# arduino_Uno_shield_bora_lora.net
KiCad netlist of a schematic drawn in EAGLE
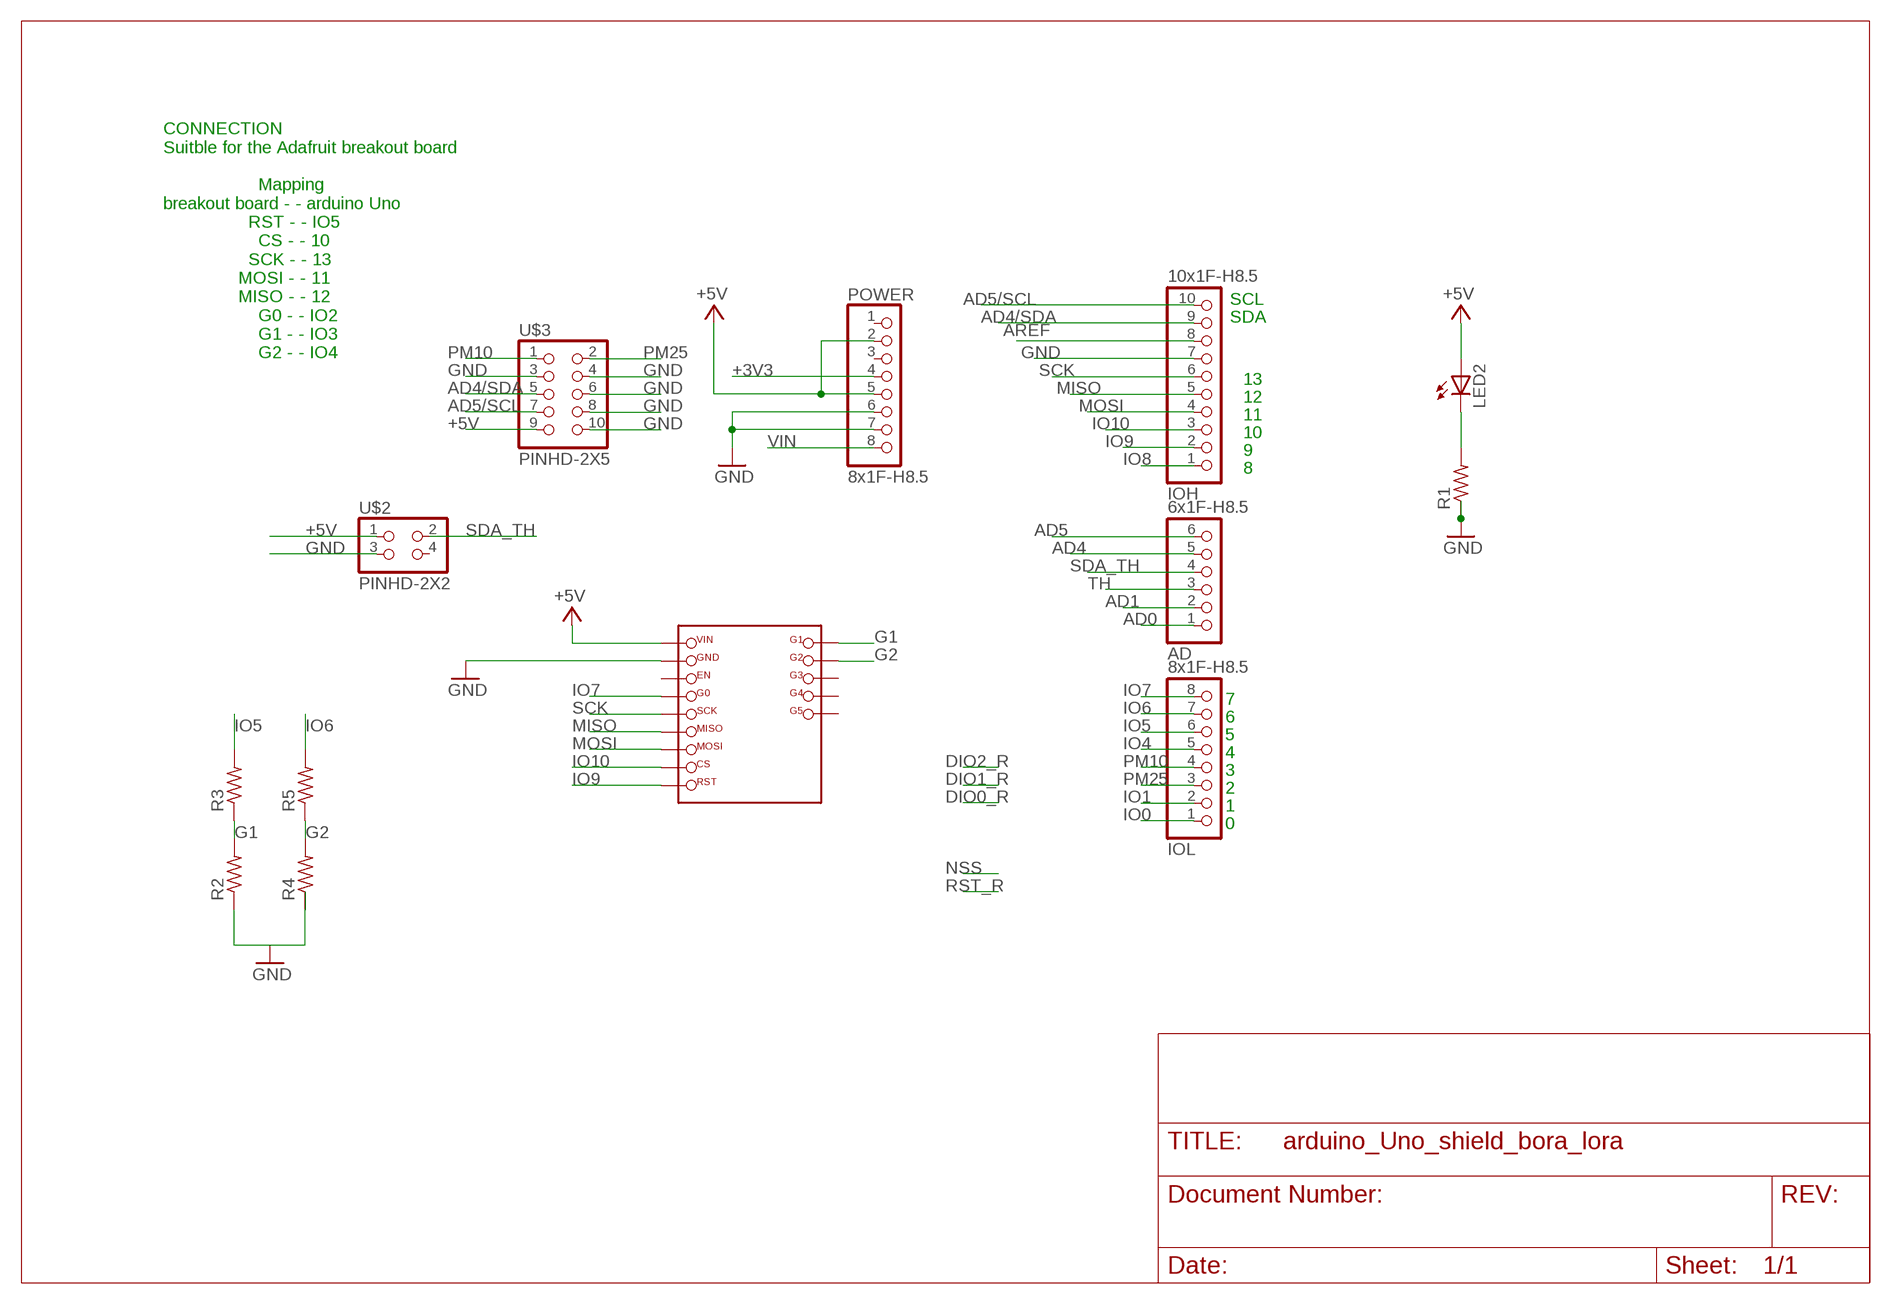
[diagram p0: schematic, sheet 1]

(export (version "E")
  (design (tool "Eeschema 10.0.6"))
  (components
    (comp (ref "AD")
      (value "6x1F-H8.5")
      (footprint "eagle-import:1X06")
      (libsource (lib "eagle-import") (part "PINHD-1X6"))
    )
    (comp (ref "IOH")
      (value "10x1F-H8.5")
      (footprint "eagle-import:1X10")
      (libsource (lib "eagle-import") (part "PINHD-1X10_ARD"))
    )
    (comp (ref "IOL")
      (value "8x1F-H8.5")
      (footprint "eagle-import:1X08")
      (libsource (lib "eagle-import") (part "PINHD-1X8"))
    )
    (comp (ref "LED2")
      (value "LED3MM")
      (footprint "eagle-import:LED3MM")
      (libsource (lib "eagle-import") (part "LED3MM"))
    )
    (comp (ref "POWER")
      (value "8x1F-H8.5")
      (footprint "eagle-import:1X08")
      (libsource (lib "eagle-import") (part "PINHD-1X8"))
    )
    (comp (ref "R1")
      (value "RESISTOR1206")
      (footprint "eagle-import:1206")
      (libsource (lib "eagle-import") (part "RESISTOR1206"))
    )
    (comp (ref "R2")
      (value "RESISTOR1206")
      (footprint "eagle-import:1206")
      (libsource (lib "eagle-import") (part "RESISTOR1206"))
    )
    (comp (ref "R3")
      (value "RESISTOR1206")
      (footprint "eagle-import:1206")
      (libsource (lib "eagle-import") (part "RESISTOR1206"))
    )
    (comp (ref "R4")
      (value "RESISTOR1206")
      (footprint "eagle-import:1206")
      (libsource (lib "eagle-import") (part "RESISTOR1206"))
    )
    (comp (ref "R5")
      (value "RESISTOR1206")
      (footprint "eagle-import:1206")
      (libsource (lib "eagle-import") (part "RESISTOR1206"))
    )
    (comp (ref "U$1")
      (value "RFM95W_ADAFRUIT")
      (footprint "eagle-import:RFM95W_ADAFRUIT")
      (libsource (lib "eagle-import") (part "RFM95W_ADAFRUIT"))
    )
    (comp (ref "U$2")
      (value "PINHD-2X2")
      (footprint "eagle-import:2X2")
      (libsource (lib "eagle-import") (part "PINHD-2X2"))
    )
    (comp (ref "U$3")
      (value "PINHD-2X5")
      (footprint "eagle-import:2X5")
      (libsource (lib "eagle-import") (part "PINHD-2X5"))
    )
  )
  (nets
    (net (code "1") (name "+5V") (class "Default")
      (node (ref "LED2") (pin "A") (pinfunction "A_A") (pintype "passive"))
      (node (ref "POWER") (pin "2") (pinfunction "2_2") (pintype "passive"))
      (node (ref "POWER") (pin "5") (pinfunction "5_5") (pintype "passive"))
      (node (ref "U$1") (pin "VIN") (pinfunction "VIN_VIN") (pintype "bidirectional"))
      (node (ref "U$2") (pin "1") (pinfunction "1_1") (pintype "passive"))
      (node (ref "U$3") (pin "9") (pinfunction "9_9") (pintype "passive"))
    )
    (net (code "2") (name "/+3V3") (class "Default")
      (node (ref "POWER") (pin "4") (pinfunction "4_4") (pintype "passive"))
    )
    (net (code "3") (name "/AD0") (class "Default")
      (node (ref "AD") (pin "1") (pinfunction "1_1") (pintype "passive"))
    )
    (net (code "4") (name "/AD1") (class "Default")
      (node (ref "AD") (pin "2") (pinfunction "2_2") (pintype "passive"))
    )
    (net (code "5") (name "/AD4") (class "Default")
      (node (ref "AD") (pin "5") (pinfunction "5_5") (pintype "passive"))
    )
    (net (code "6") (name "/AD4{slash}SDA") (class "Default")
      (node (ref "IOH") (pin "9") (pinfunction "9_9") (pintype "passive"))
      (node (ref "U$3") (pin "5") (pinfunction "5_5") (pintype "passive"))
    )
    (net (code "7") (name "/AD5") (class "Default")
      (node (ref "AD") (pin "6") (pinfunction "6_6") (pintype "passive"))
    )
    (net (code "8") (name "/AD5{slash}SCL") (class "Default")
      (node (ref "IOH") (pin "10") (pinfunction "10_10") (pintype "passive"))
      (node (ref "U$3") (pin "7") (pinfunction "7_7") (pintype "passive"))
    )
    (net (code "9") (name "/AREF") (class "Default")
      (node (ref "IOH") (pin "8") (pinfunction "8_8") (pintype "passive"))
    )
    (net (code "13") (name "/G1") (class "Default")
      (node (ref "R2") (pin "2") (pinfunction "2_2") (pintype "passive"))
      (node (ref "R3") (pin "1") (pinfunction "1_1") (pintype "passive"))
      (node (ref "U$1") (pin "G1") (pinfunction "G1_G1") (pintype "bidirectional"))
    )
    (net (code "14") (name "/G2") (class "Default")
      (node (ref "R4") (pin "2") (pinfunction "2_2") (pintype "passive"))
      (node (ref "R5") (pin "1") (pinfunction "1_1") (pintype "passive"))
      (node (ref "U$1") (pin "G2") (pinfunction "G2_G2") (pintype "bidirectional"))
    )
    (net (code "15") (name "/IO0") (class "Default")
      (node (ref "IOL") (pin "1") (pinfunction "1_1") (pintype "passive"))
    )
    (net (code "16") (name "/IO1") (class "Default")
      (node (ref "IOL") (pin "2") (pinfunction "2_2") (pintype "passive"))
    )
    (net (code "17") (name "/IO4") (class "Default")
      (node (ref "IOL") (pin "5") (pinfunction "5_5") (pintype "passive"))
    )
    (net (code "18") (name "/IO5") (class "Default")
      (node (ref "IOL") (pin "6") (pinfunction "6_6") (pintype "passive"))
      (node (ref "R3") (pin "2") (pinfunction "2_2") (pintype "passive"))
    )
    (net (code "19") (name "/IO6") (class "Default")
      (node (ref "IOL") (pin "7") (pinfunction "7_7") (pintype "passive"))
      (node (ref "R5") (pin "2") (pinfunction "2_2") (pintype "passive"))
    )
    (net (code "20") (name "/IO7") (class "Default")
      (node (ref "IOL") (pin "8") (pinfunction "8_8") (pintype "passive"))
      (node (ref "U$1") (pin "G0") (pinfunction "G0_G0") (pintype "bidirectional"))
    )
    (net (code "21") (name "/IO8") (class "Default")
      (node (ref "IOH") (pin "1") (pinfunction "1_1") (pintype "passive"))
    )
    (net (code "22") (name "/IO9") (class "Default")
      (node (ref "IOH") (pin "2") (pinfunction "2_2") (pintype "passive"))
      (node (ref "U$1") (pin "RST") (pinfunction "RST_RST") (pintype "bidirectional"))
    )
    (net (code "23") (name "/IO10") (class "Default")
      (node (ref "IOH") (pin "3") (pinfunction "3_3") (pintype "passive"))
      (node (ref "U$1") (pin "CS") (pinfunction "CS_CS") (pintype "bidirectional"))
    )
    (net (code "24") (name "/MISO") (class "Default")
      (node (ref "IOH") (pin "5") (pinfunction "5_5") (pintype "passive"))
      (node (ref "U$1") (pin "MISO") (pinfunction "MISO_MISO") (pintype "bidirectional"))
    )
    (net (code "25") (name "/MOSI") (class "Default")
      (node (ref "IOH") (pin "4") (pinfunction "4_4") (pintype "passive"))
      (node (ref "U$1") (pin "MOSI") (pinfunction "MOSI_MOSI") (pintype "bidirectional"))
    )
    (net (code "27") (name "/PM10") (class "Default")
      (node (ref "IOL") (pin "4") (pinfunction "4_4") (pintype "passive"))
      (node (ref "U$3") (pin "1") (pinfunction "1_1") (pintype "passive"))
    )
    (net (code "28") (name "/PM25") (class "Default")
      (node (ref "IOL") (pin "3") (pinfunction "3_3") (pintype "passive"))
      (node (ref "U$3") (pin "2") (pinfunction "2_2") (pintype "passive"))
    )
    (net (code "30") (name "/SCK") (class "Default")
      (node (ref "IOH") (pin "6") (pinfunction "6_6") (pintype "passive"))
      (node (ref "U$1") (pin "SCK") (pinfunction "SCK_SCK") (pintype "bidirectional"))
    )
    (net (code "31") (name "/SDA_TH") (class "Default")
      (node (ref "AD") (pin "4") (pinfunction "4_4") (pintype "passive"))
      (node (ref "U$2") (pin "2") (pinfunction "2_2") (pintype "passive"))
    )
    (net (code "32") (name "/TH") (class "Default")
      (node (ref "AD") (pin "3") (pinfunction "3_3") (pintype "passive"))
    )
    (net (code "33") (name "/VIN") (class "Default")
      (node (ref "POWER") (pin "8") (pinfunction "8_8") (pintype "passive"))
    )
    (net (code "34") (name "GND") (class "Default")
      (node (ref "IOH") (pin "7") (pinfunction "7_7") (pintype "passive"))
      (node (ref "POWER") (pin "6") (pinfunction "6_6") (pintype "passive"))
      (node (ref "POWER") (pin "7") (pinfunction "7_7") (pintype "passive"))
      (node (ref "R1") (pin "1") (pinfunction "1_1") (pintype "passive"))
      (node (ref "R2") (pin "1") (pinfunction "1_1") (pintype "passive"))
      (node (ref "R4") (pin "1") (pinfunction "1_1") (pintype "passive"))
      (node (ref "U$1") (pin "GND") (pinfunction "GND_GND") (pintype "bidirectional"))
      (node (ref "U$2") (pin "3") (pinfunction "3_3") (pintype "passive"))
      (node (ref "U$3") (pin "10") (pinfunction "10_10") (pintype "passive"))
      (node (ref "U$3") (pin "3") (pinfunction "3_3") (pintype "passive"))
      (node (ref "U$3") (pin "4") (pinfunction "4_4") (pintype "passive"))
      (node (ref "U$3") (pin "6") (pinfunction "6_6") (pintype "passive"))
      (node (ref "U$3") (pin "8") (pinfunction "8_8") (pintype "passive"))
    )
    (net (code "35") (name "Net-(LED2-C)") (class "Default")
      (node (ref "LED2") (pin "K") (pinfunction "C_K") (pintype "passive"))
      (node (ref "R1") (pin "2") (pinfunction "2_2") (pintype "passive"))
    )
    (net (code "36") (name "unconnected-(POWER-Pad1)") (class "Default")
      (node (ref "POWER") (pin "1") (pinfunction "1_1") (pintype "passive"))
    )
    (net (code "37") (name "unconnected-(POWER-Pad3)") (class "Default")
      (node (ref "POWER") (pin "3") (pinfunction "3_3") (pintype "passive"))
    )
    (net (code "38") (name "unconnected-(U$1-PadEN)") (class "Default")
      (node (ref "U$1") (pin "EN") (pinfunction "EN_EN") (pintype "bidirectional"))
    )
    (net (code "39") (name "unconnected-(U$1-PadG3)") (class "Default")
      (node (ref "U$1") (pin "G3") (pinfunction "G3_G3") (pintype "bidirectional"))
    )
    (net (code "40") (name "unconnected-(U$1-PadG4)") (class "Default")
      (node (ref "U$1") (pin "G4") (pinfunction "G4_G4") (pintype "bidirectional"))
    )
    (net (code "41") (name "unconnected-(U$1-PadG5)") (class "Default")
      (node (ref "U$1") (pin "G5") (pinfunction "G5_G5") (pintype "bidirectional"))
    )
    (net (code "42") (name "unconnected-(U$2-Pad4)") (class "Default")
      (node (ref "U$2") (pin "4") (pinfunction "4_4") (pintype "passive"))
    )
  )
)
